# SCH_ACSI2STM_EasyEDA.net
KiCad netlist of a schematic drawn in EasyEDA
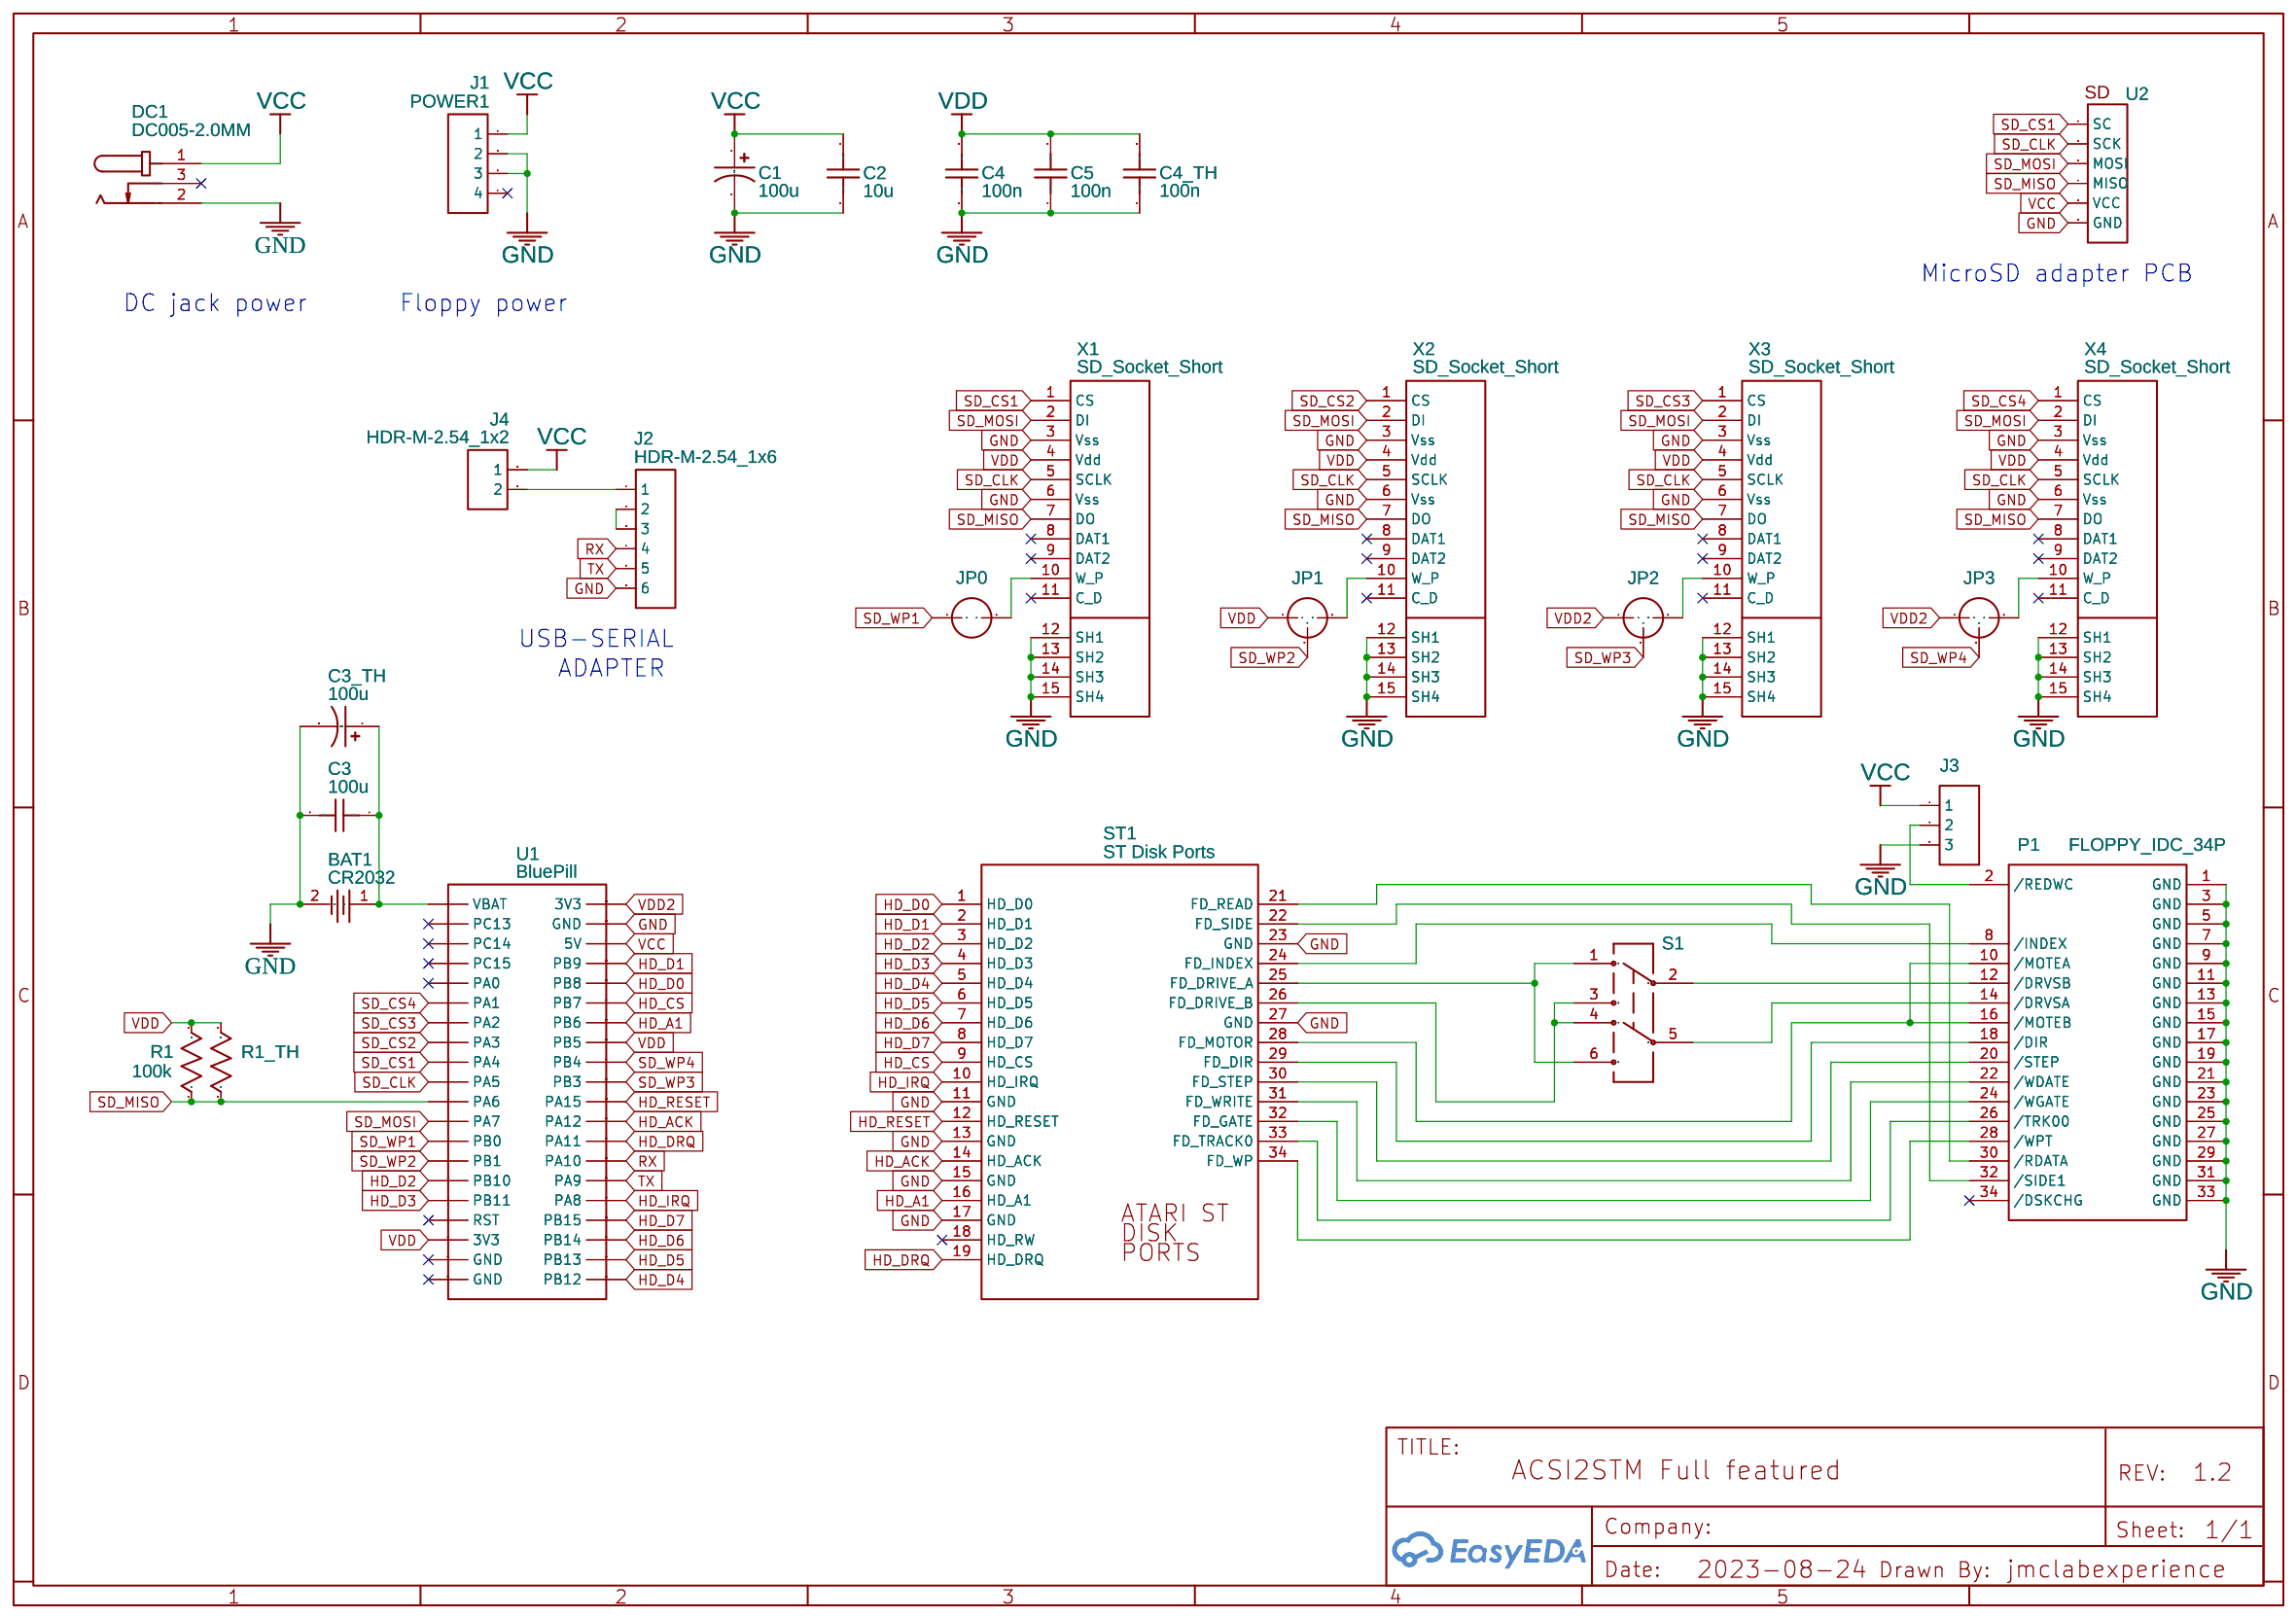
[diagram p0: schematic sheet]

(export (version "E")
  (design (tool "Eeschema 10.0.6"))
  (components
    (comp (ref "BAT1") (value "CR2032") (libsource (lib "") (part "CR2032_C9900007674")))
    (comp (ref "C1") (value "100u") (libsource (lib "") (part "CE_TH_D6.3×F2.5_US_1")))
    (comp (ref "C2") (value "10u") (libsource (lib "") (part "C_1206_US_1")))
    (comp (ref "C3") (value "100u") (libsource (lib "") (part "C_1206_US")))
    (comp (ref "C3_TH") (value "100u") (libsource (lib "") (part "CE_TH_D6.3×F2.5_US")))
    (comp (ref "C4") (value "100n") (libsource (lib "") (part "C_0805_US")))
    (comp (ref "C4_TH") (value "100n") (libsource (lib "") (part "C_RAD-0.2_US")))
    (comp (ref "C5") (value "100n") (libsource (lib "") (part "C_0805_US")))
    (comp (ref "DC1")
      (value "DC005-2.0MM")
      (fields (field (name "Manufacturer") "SOFNG"))
      (libsource (lib "") (part "DC005-2.0MM"))
    )
    (comp (ref "J1") (value "POWER1") (libsource (lib "") (part "HDR-M-2.54_1x4")))
    (comp (ref "J2") (value "HDR-M-2.54_1x6") (libsource (lib "") (part "HDR-M-2.54_1x6")))
    (comp (ref "J3") (value "HDR-M-2.54_1x3") (libsource (lib "") (part "HDR-M-2.54_1x3")))
    (comp (ref "J4") (value "HDR-M-2.54_1x2") (libsource (lib "") (part "HDR-M-2.54_1x2")))
    (comp (ref "JP0") (value "Solder jumper 2P") (libsource (lib "") (part "Solder jumper 2P")))
    (comp (ref "JP1") (value "Solder jumper 3P") (libsource (lib "") (part "Solder jumper 3P")))
    (comp (ref "JP2") (value "Solder jumper 3P") (libsource (lib "") (part "Solder jumper 3P")))
    (comp (ref "JP3") (value "Solder jumper 3P") (libsource (lib "") (part "Solder jumper 3P")))
    (comp (ref "P1")
      (value "FLOPPY_IDC_34P")
      (fields (field (name "Manufacturer Part") "Z-231011034106") (field (name "Manufacturer") "Nextronics"))
      (libsource (lib "") (part "FLOPPY_IDC_34P"))
    )
    (comp (ref "R1") (value "100k") (libsource (lib "") (part "R_0805_US")))
    (comp (ref "R1_TH") (value "1k") (libsource (lib "") (part "R_AXIAL-0.4_US")))
    (comp (ref "S1") (value "SWITCH-DPDT") (libsource (lib "") (part "SWITCH-DPDT")))
    (comp (ref "ST1") (value "ST Disk Ports") (libsource (lib "") (part "ST Disk Ports")))
    (comp (ref "U1") (value "BluePill") (libsource (lib "") (part "BluePill")))
    (comp (ref "U2") (value "SD1") (libsource (lib "") (part "SD")))
    (comp (ref "X1") (value "SD_Socket_Short") (libsource (lib "") (part "SD_Socket_Short")))
    (comp (ref "X2") (value "SD_Socket_Short") (libsource (lib "") (part "SD_Socket_Short")))
    (comp (ref "X3") (value "SD_Socket_Short") (libsource (lib "") (part "SD_Socket_Short")))
    (comp (ref "X4") (value "SD_Socket_Short") (libsource (lib "") (part "SD_Socket_Short")))
  )
  (nets
    (net (code "1") (name "GND") (class "Default")
      (node (ref "BAT1") (pin "2") (pinfunction "2_2") (pintype "input"))
      (node (ref "C1") (pin "2") (pinfunction "2_2") (pintype "unspecified"))
      (node (ref "C2") (pin "1") (pinfunction "1_1") (pintype "unspecified"))
      (node (ref "C3") (pin "2") (pinfunction "2_2") (pintype "unspecified"))
      (node (ref "C3_TH") (pin "2") (pinfunction "2_2") (pintype "unspecified"))
      (node (ref "C4") (pin "1") (pinfunction "1_1") (pintype "unspecified"))
      (node (ref "C4_TH") (pin "1") (pinfunction "1_1") (pintype "unspecified"))
      (node (ref "C5") (pin "1") (pinfunction "1_1") (pintype "unspecified"))
      (node (ref "DC1") (pin "2") (pinfunction "2_2") (pintype "unspecified"))
      (node (ref "J1") (pin "2") (pinfunction "2_2") (pintype "unspecified"))
      (node (ref "J1") (pin "3") (pinfunction "3_3") (pintype "unspecified"))
      (node (ref "J2") (pin "6") (pinfunction "6_6") (pintype "input"))
      (node (ref "J3") (pin "3") (pinfunction "3_3") (pintype "input"))
      (node (ref "P1") (pin "1") (pinfunction "GND_1") (pintype "unspecified"))
      (node (ref "P1") (pin "11") (pinfunction "GND_11") (pintype "unspecified"))
      (node (ref "P1") (pin "13") (pinfunction "GND_13") (pintype "unspecified"))
      (node (ref "P1") (pin "15") (pinfunction "GND_15") (pintype "unspecified"))
      (node (ref "P1") (pin "17") (pinfunction "GND_17") (pintype "unspecified"))
      (node (ref "P1") (pin "19") (pinfunction "GND_19") (pintype "unspecified"))
      (node (ref "P1") (pin "21") (pinfunction "GND_21") (pintype "unspecified"))
      (node (ref "P1") (pin "23") (pinfunction "GND_23") (pintype "unspecified"))
      (node (ref "P1") (pin "25") (pinfunction "GND_25") (pintype "unspecified"))
      (node (ref "P1") (pin "27") (pinfunction "GND_27") (pintype "unspecified"))
      (node (ref "P1") (pin "29") (pinfunction "GND_29") (pintype "unspecified"))
      (node (ref "P1") (pin "3") (pinfunction "GND_3") (pintype "unspecified"))
      (node (ref "P1") (pin "31") (pinfunction "GND_31") (pintype "unspecified"))
      (node (ref "P1") (pin "33") (pinfunction "GND_33") (pintype "unspecified"))
      (node (ref "P1") (pin "5") (pinfunction "GND_5") (pintype "unspecified"))
      (node (ref "P1") (pin "7") (pinfunction "GND_7") (pintype "unspecified"))
      (node (ref "P1") (pin "9") (pinfunction "GND_9") (pintype "unspecified"))
      (node (ref "ST1") (pin "11") (pinfunction "GND_11") (pintype "unspecified"))
      (node (ref "ST1") (pin "13") (pinfunction "GND_13") (pintype "unspecified"))
      (node (ref "ST1") (pin "15") (pinfunction "GND_15") (pintype "unspecified"))
      (node (ref "ST1") (pin "17") (pinfunction "GND_17") (pintype "unspecified"))
      (node (ref "ST1") (pin "23") (pinfunction "GND_23") (pintype "unspecified"))
      (node (ref "ST1") (pin "27") (pinfunction "GND_27") (pintype "unspecified"))
      (node (ref "U1") (pin "GND_3") (pinfunction "GND_GND_3") (pintype "unspecified"))
      (node (ref "U2") (pin "6") (pinfunction "GND_6") (pintype "input"))
      (node (ref "X1") (pin "12") (pinfunction "SH1_12") (pintype "unspecified"))
      (node (ref "X1") (pin "13") (pinfunction "SH2_13") (pintype "unspecified"))
      (node (ref "X1") (pin "14") (pinfunction "SH3_14") (pintype "unspecified"))
      (node (ref "X1") (pin "15") (pinfunction "SH4_15") (pintype "unspecified"))
      (node (ref "X1") (pin "3") (pinfunction "Vss_3") (pintype "unspecified"))
      (node (ref "X1") (pin "6") (pinfunction "Vss_6") (pintype "unspecified"))
      (node (ref "X2") (pin "12") (pinfunction "SH1_12") (pintype "unspecified"))
      (node (ref "X2") (pin "13") (pinfunction "SH2_13") (pintype "unspecified"))
      (node (ref "X2") (pin "14") (pinfunction "SH3_14") (pintype "unspecified"))
      (node (ref "X2") (pin "15") (pinfunction "SH4_15") (pintype "unspecified"))
      (node (ref "X2") (pin "3") (pinfunction "Vss_3") (pintype "unspecified"))
      (node (ref "X2") (pin "6") (pinfunction "Vss_6") (pintype "unspecified"))
      (node (ref "X3") (pin "12") (pinfunction "SH1_12") (pintype "unspecified"))
      (node (ref "X3") (pin "13") (pinfunction "SH2_13") (pintype "unspecified"))
      (node (ref "X3") (pin "14") (pinfunction "SH3_14") (pintype "unspecified"))
      (node (ref "X3") (pin "15") (pinfunction "SH4_15") (pintype "unspecified"))
      (node (ref "X3") (pin "3") (pinfunction "Vss_3") (pintype "unspecified"))
      (node (ref "X3") (pin "6") (pinfunction "Vss_6") (pintype "unspecified"))
      (node (ref "X4") (pin "12") (pinfunction "SH1_12") (pintype "unspecified"))
      (node (ref "X4") (pin "13") (pinfunction "SH2_13") (pintype "unspecified"))
      (node (ref "X4") (pin "14") (pinfunction "SH3_14") (pintype "unspecified"))
      (node (ref "X4") (pin "15") (pinfunction "SH4_15") (pintype "unspecified"))
      (node (ref "X4") (pin "3") (pinfunction "Vss_3") (pintype "unspecified"))
      (node (ref "X4") (pin "6") (pinfunction "Vss_6") (pintype "unspecified"))
    )
    (net (code "2") (name "HD_A1") (class "Default")
      (node (ref "ST1") (pin "16") (pinfunction "HD_A1_16") (pintype "unspecified"))
      (node (ref "U1") (pin "PB6") (pinfunction "PB6_PB6") (pintype "unspecified"))
    )
    (net (code "3") (name "HD_ACK") (class "Default")
      (node (ref "ST1") (pin "14") (pinfunction "HD_ACK_14") (pintype "unspecified"))
      (node (ref "U1") (pin "PA12") (pinfunction "PA12_PA12") (pintype "unspecified"))
    )
    (net (code "4") (name "HD_CS") (class "Default")
      (node (ref "ST1") (pin "9") (pinfunction "HD_CS_9") (pintype "unspecified"))
      (node (ref "U1") (pin "PB7") (pinfunction "PB7_PB7") (pintype "unspecified"))
    )
    (net (code "5") (name "HD_D0") (class "Default")
      (node (ref "ST1") (pin "1") (pinfunction "HD_D0_1") (pintype "unspecified"))
      (node (ref "U1") (pin "PB8") (pinfunction "PB8_PB8") (pintype "unspecified"))
    )
    (net (code "6") (name "HD_D1") (class "Default")
      (node (ref "ST1") (pin "2") (pinfunction "HD_D1_2") (pintype "unspecified"))
      (node (ref "U1") (pin "PB9") (pinfunction "PB9_PB9") (pintype "unspecified"))
    )
    (net (code "7") (name "HD_D2") (class "Default")
      (node (ref "ST1") (pin "3") (pinfunction "HD_D2_3") (pintype "unspecified"))
      (node (ref "U1") (pin "PB10") (pinfunction "PB10_PB10") (pintype "unspecified"))
    )
    (net (code "8") (name "HD_D3") (class "Default")
      (node (ref "ST1") (pin "4") (pinfunction "HD_D3_4") (pintype "unspecified"))
      (node (ref "U1") (pin "PB11") (pinfunction "PB11_PB11") (pintype "unspecified"))
    )
    (net (code "9") (name "HD_D4") (class "Default")
      (node (ref "ST1") (pin "5") (pinfunction "HD_D4_5") (pintype "unspecified"))
      (node (ref "U1") (pin "PB12") (pinfunction "PB12_PB12") (pintype "unspecified"))
    )
    (net (code "10") (name "HD_D5") (class "Default")
      (node (ref "ST1") (pin "6") (pinfunction "HD_D5_6") (pintype "unspecified"))
      (node (ref "U1") (pin "PB13") (pinfunction "PB13_PB13") (pintype "unspecified"))
    )
    (net (code "11") (name "HD_D6") (class "Default")
      (node (ref "ST1") (pin "7") (pinfunction "HD_D6_7") (pintype "unspecified"))
      (node (ref "U1") (pin "PB14") (pinfunction "PB14_PB14") (pintype "unspecified"))
    )
    (net (code "12") (name "HD_D7") (class "Default")
      (node (ref "ST1") (pin "8") (pinfunction "HD_D7_8") (pintype "unspecified"))
      (node (ref "U1") (pin "PB15") (pinfunction "PB15_PB15") (pintype "unspecified"))
    )
    (net (code "13") (name "HD_DRQ") (class "Default")
      (node (ref "ST1") (pin "19") (pinfunction "HD_DRQ_19") (pintype "unspecified"))
      (node (ref "U1") (pin "PA11") (pinfunction "PA11_PA11") (pintype "unspecified"))
    )
    (net (code "14") (name "HD_IRQ") (class "Default")
      (node (ref "ST1") (pin "10") (pinfunction "HD_IRQ_10") (pintype "unspecified"))
      (node (ref "U1") (pin "PA8") (pinfunction "PA8_PA8") (pintype "unspecified"))
    )
    (net (code "15") (name "HD_RESET") (class "Default")
      (node (ref "ST1") (pin "12") (pinfunction "HD_RESET_12") (pintype "unspecified"))
      (node (ref "U1") (pin "PA15") (pinfunction "PA15_PA15") (pintype "unspecified"))
    )
    (net (code "16") (name "Net-(BAT1-Pad1)") (class "Default")
      (node (ref "BAT1") (pin "1") (pinfunction "1_1") (pintype "input"))
      (node (ref "C3") (pin "1") (pinfunction "1_1") (pintype "unspecified"))
      (node (ref "C3_TH") (pin "1") (pinfunction "1_1") (pintype "unspecified"))
      (node (ref "U1") (pin "VBAT") (pinfunction "VBAT_VBAT") (pintype "unspecified"))
    )
    (net (code "17") (name "Net-(J2-Pad1)") (class "Default")
      (node (ref "J2") (pin "1") (pinfunction "1_1") (pintype "input"))
      (node (ref "J4") (pin "2") (pinfunction "2_2") (pintype "unspecified"))
    )
    (net (code "18") (name "Net-(J2-Pad2)") (class "Default")
      (node (ref "J2") (pin "2") (pinfunction "2_2") (pintype "input"))
      (node (ref "J2") (pin "3") (pinfunction "3_3") (pintype "input"))
    )
    (net (code "19") (name "Net-(P1-{slash}DIR)") (class "Default")
      (node (ref "P1") (pin "18") (pinfunction "/DIR_18") (pintype "unspecified"))
      (node (ref "ST1") (pin "29") (pinfunction "FD_DIR_29") (pintype "unspecified"))
    )
    (net (code "20") (name "Net-(P1-{slash}DRVSA)") (class "Default")
      (node (ref "P1") (pin "14") (pinfunction "/DRVSA_14") (pintype "unspecified"))
      (node (ref "S1") (pin "5") (pinfunction "5_5") (pintype "unspecified"))
    )
    (net (code "21") (name "Net-(P1-{slash}DRVSB)") (class "Default")
      (node (ref "P1") (pin "12") (pinfunction "/DRVSB_12") (pintype "unspecified"))
      (node (ref "S1") (pin "2") (pinfunction "2_2") (pintype "unspecified"))
    )
    (net (code "22") (name "Net-(P1-{slash}INDEX)") (class "Default")
      (node (ref "P1") (pin "8") (pinfunction "/INDEX_8") (pintype "unspecified"))
      (node (ref "ST1") (pin "24") (pinfunction "FD_INDEX_24") (pintype "unspecified"))
    )
    (net (code "23") (name "Net-(P1-{slash}MOTEA)") (class "Default")
      (node (ref "P1") (pin "10") (pinfunction "/MOTEA_10") (pintype "unspecified"))
      (node (ref "P1") (pin "16") (pinfunction "/MOTEB_16") (pintype "unspecified"))
      (node (ref "ST1") (pin "28") (pinfunction "FD_MOTOR_28") (pintype "unspecified"))
    )
    (net (code "24") (name "Net-(P1-{slash}RDATA)") (class "Default")
      (node (ref "P1") (pin "30") (pinfunction "/RDATA_30") (pintype "unspecified"))
      (node (ref "ST1") (pin "21") (pinfunction "FD_READ_21") (pintype "unspecified"))
    )
    (net (code "25") (name "Net-(P1-{slash}REDWC)") (class "Default")
      (node (ref "J3") (pin "2") (pinfunction "2_2") (pintype "input"))
      (node (ref "P1") (pin "2") (pinfunction "/REDWC_2") (pintype "unspecified"))
    )
    (net (code "26") (name "Net-(P1-{slash}SIDE1)") (class "Default")
      (node (ref "P1") (pin "32") (pinfunction "/SIDE1_32") (pintype "unspecified"))
      (node (ref "ST1") (pin "22") (pinfunction "FD_SIDE_22") (pintype "unspecified"))
    )
    (net (code "27") (name "Net-(P1-{slash}STEP)") (class "Default")
      (node (ref "P1") (pin "20") (pinfunction "/STEP_20") (pintype "unspecified"))
      (node (ref "ST1") (pin "30") (pinfunction "FD_STEP_30") (pintype "unspecified"))
    )
    (net (code "28") (name "Net-(P1-{slash}TRK00)") (class "Default")
      (node (ref "P1") (pin "26") (pinfunction "/TRK00_26") (pintype "unspecified"))
      (node (ref "ST1") (pin "33") (pinfunction "FD_TRACK0_33") (pintype "unspecified"))
    )
    (net (code "29") (name "Net-(P1-{slash}WDATE)") (class "Default")
      (node (ref "P1") (pin "22") (pinfunction "/WDATE_22") (pintype "unspecified"))
      (node (ref "ST1") (pin "31") (pinfunction "FD_WRITE_31") (pintype "unspecified"))
    )
    (net (code "30") (name "Net-(P1-{slash}WGATE)") (class "Default")
      (node (ref "P1") (pin "24") (pinfunction "/WGATE_24") (pintype "unspecified"))
      (node (ref "ST1") (pin "32") (pinfunction "FD_GATE_32") (pintype "unspecified"))
    )
    (net (code "31") (name "Net-(P1-{slash}WPT)") (class "Default")
      (node (ref "P1") (pin "28") (pinfunction "/WPT_28") (pintype "unspecified"))
      (node (ref "ST1") (pin "34") (pinfunction "FD_WP_34") (pintype "unspecified"))
    )
    (net (code "32") (name "Net-(ST1-FD_DRIVE_A)") (class "Default")
      (node (ref "S1") (pin "1") (pinfunction "1_1") (pintype "unspecified"))
      (node (ref "S1") (pin "6") (pinfunction "6_6") (pintype "unspecified"))
      (node (ref "ST1") (pin "25") (pinfunction "FD_DRIVE_A_25") (pintype "unspecified"))
    )
    (net (code "33") (name "Net-(ST1-FD_DRIVE_B)") (class "Default")
      (node (ref "S1") (pin "3") (pinfunction "3_3") (pintype "unspecified"))
      (node (ref "S1") (pin "4") (pinfunction "4_4") (pintype "unspecified"))
      (node (ref "ST1") (pin "26") (pinfunction "FD_DRIVE_B_26") (pintype "unspecified"))
    )
    (net (code "34") (name "Net-(X1-W_P)") (class "Default")
      (node (ref "JP0") (pin "2") (pinfunction "2_2") (pintype "unspecified"))
      (node (ref "X1") (pin "10") (pinfunction "W_P_10") (pintype "unspecified"))
    )
    (net (code "35") (name "Net-(X2-W_P)") (class "Default")
      (node (ref "JP1") (pin "3") (pinfunction "3_3") (pintype "unspecified"))
      (node (ref "X2") (pin "10") (pinfunction "W_P_10") (pintype "unspecified"))
    )
    (net (code "36") (name "Net-(X3-W_P)") (class "Default")
      (node (ref "JP2") (pin "3") (pinfunction "3_3") (pintype "unspecified"))
      (node (ref "X3") (pin "10") (pinfunction "W_P_10") (pintype "unspecified"))
    )
    (net (code "37") (name "Net-(X4-W_P)") (class "Default")
      (node (ref "JP3") (pin "3") (pinfunction "3_3") (pintype "unspecified"))
      (node (ref "X4") (pin "10") (pinfunction "W_P_10") (pintype "unspecified"))
    )
    (net (code "38") (name "RX") (class "Default")
      (node (ref "J2") (pin "4") (pinfunction "4_4") (pintype "input"))
      (node (ref "U1") (pin "PA10") (pinfunction "PA10_PA10") (pintype "unspecified"))
    )
    (net (code "39") (name "SD_CLK") (class "Default")
      (node (ref "U1") (pin "PA5") (pinfunction "PA5_PA5") (pintype "unspecified"))
      (node (ref "U2") (pin "2") (pinfunction "SCK_2") (pintype "input"))
      (node (ref "X1") (pin "5") (pinfunction "SCLK_5") (pintype "unspecified"))
      (node (ref "X2") (pin "5") (pinfunction "SCLK_5") (pintype "unspecified"))
      (node (ref "X3") (pin "5") (pinfunction "SCLK_5") (pintype "unspecified"))
      (node (ref "X4") (pin "5") (pinfunction "SCLK_5") (pintype "unspecified"))
    )
    (net (code "40") (name "SD_CS1") (class "Default")
      (node (ref "U1") (pin "PA4") (pinfunction "PA4_PA4") (pintype "unspecified"))
      (node (ref "U2") (pin "1") (pinfunction "SC_1") (pintype "input"))
      (node (ref "X1") (pin "1") (pinfunction "CS_1") (pintype "unspecified"))
    )
    (net (code "41") (name "SD_CS2") (class "Default")
      (node (ref "U1") (pin "PA3") (pinfunction "PA3_PA3") (pintype "unspecified"))
      (node (ref "X2") (pin "1") (pinfunction "CS_1") (pintype "unspecified"))
    )
    (net (code "42") (name "SD_CS3") (class "Default")
      (node (ref "U1") (pin "PA2") (pinfunction "PA2_PA2") (pintype "unspecified"))
      (node (ref "X3") (pin "1") (pinfunction "CS_1") (pintype "unspecified"))
    )
    (net (code "43") (name "SD_CS4") (class "Default")
      (node (ref "U1") (pin "PA1") (pinfunction "PA1_PA1") (pintype "unspecified"))
      (node (ref "X4") (pin "1") (pinfunction "CS_1") (pintype "unspecified"))
    )
    (net (code "44") (name "SD_MISO") (class "Default")
      (node (ref "R1") (pin "1") (pinfunction "1_1") (pintype "unspecified"))
      (node (ref "R1_TH") (pin "1") (pinfunction "1_1") (pintype "unspecified"))
      (node (ref "U1") (pin "PA6") (pinfunction "PA6_PA6") (pintype "unspecified"))
      (node (ref "U2") (pin "4") (pinfunction "MISO_4") (pintype "input"))
      (node (ref "X1") (pin "7") (pinfunction "DO_7") (pintype "unspecified"))
      (node (ref "X2") (pin "7") (pinfunction "DO_7") (pintype "unspecified"))
      (node (ref "X3") (pin "7") (pinfunction "DO_7") (pintype "unspecified"))
      (node (ref "X4") (pin "7") (pinfunction "DO_7") (pintype "unspecified"))
    )
    (net (code "45") (name "SD_MOSI") (class "Default")
      (node (ref "U1") (pin "PA7") (pinfunction "PA7_PA7") (pintype "unspecified"))
      (node (ref "U2") (pin "3") (pinfunction "MOSI_3") (pintype "input"))
      (node (ref "X1") (pin "2") (pinfunction "DI_2") (pintype "unspecified"))
      (node (ref "X2") (pin "2") (pinfunction "DI_2") (pintype "unspecified"))
      (node (ref "X3") (pin "2") (pinfunction "DI_2") (pintype "unspecified"))
      (node (ref "X4") (pin "2") (pinfunction "DI_2") (pintype "unspecified"))
    )
    (net (code "46") (name "SD_WP1") (class "Default")
      (node (ref "JP0") (pin "1") (pinfunction "1_1") (pintype "unspecified"))
      (node (ref "U1") (pin "PB0") (pinfunction "PB0_PB0") (pintype "unspecified"))
    )
    (net (code "47") (name "SD_WP2") (class "Default")
      (node (ref "JP1") (pin "2") (pinfunction "2_2") (pintype "unspecified"))
      (node (ref "U1") (pin "PB1") (pinfunction "PB1_PB1") (pintype "unspecified"))
    )
    (net (code "48") (name "SD_WP3") (class "Default")
      (node (ref "JP2") (pin "2") (pinfunction "2_2") (pintype "unspecified"))
      (node (ref "U1") (pin "PB3") (pinfunction "PB3_PB3") (pintype "unspecified"))
    )
    (net (code "49") (name "SD_WP4") (class "Default")
      (node (ref "JP3") (pin "2") (pinfunction "2_2") (pintype "unspecified"))
      (node (ref "U1") (pin "PB4") (pinfunction "PB4_PB4") (pintype "unspecified"))
    )
    (net (code "50") (name "TX") (class "Default")
      (node (ref "J2") (pin "5") (pinfunction "5_5") (pintype "input"))
      (node (ref "U1") (pin "PA9") (pinfunction "PA9_PA9") (pintype "unspecified"))
    )
    (net (code "51") (name "VCC") (class "Default")
      (node (ref "C1") (pin "1") (pinfunction "1_1") (pintype "unspecified"))
      (node (ref "C2") (pin "2") (pinfunction "2_2") (pintype "unspecified"))
      (node (ref "DC1") (pin "1") (pinfunction "1_1") (pintype "unspecified"))
      (node (ref "J1") (pin "1") (pinfunction "1_1") (pintype "unspecified"))
      (node (ref "J3") (pin "1") (pinfunction "1_1") (pintype "input"))
      (node (ref "J4") (pin "1") (pinfunction "1_1") (pintype "unspecified"))
      (node (ref "U1") (pin "5V") (pinfunction "5V_5V") (pintype "unspecified"))
      (node (ref "U2") (pin "5") (pinfunction "VCC_5") (pintype "input"))
    )
    (net (code "52") (name "VDD") (class "Default")
      (node (ref "C4") (pin "2") (pinfunction "2_2") (pintype "unspecified"))
      (node (ref "C4_TH") (pin "2") (pinfunction "2_2") (pintype "unspecified"))
      (node (ref "C5") (pin "2") (pinfunction "2_2") (pintype "unspecified"))
      (node (ref "JP1") (pin "1") (pinfunction "1_1") (pintype "unspecified"))
      (node (ref "R1") (pin "2") (pinfunction "2_2") (pintype "unspecified"))
      (node (ref "R1_TH") (pin "2") (pinfunction "2_2") (pintype "unspecified"))
      (node (ref "U1") (pin "3V3_1") (pinfunction "3V3_3V3_1") (pintype "unspecified"))
      (node (ref "U1") (pin "PB5") (pinfunction "PB5_PB5") (pintype "unspecified"))
      (node (ref "X1") (pin "4") (pinfunction "Vdd_4") (pintype "unspecified"))
      (node (ref "X2") (pin "4") (pinfunction "Vdd_4") (pintype "unspecified"))
      (node (ref "X3") (pin "4") (pinfunction "Vdd_4") (pintype "unspecified"))
      (node (ref "X4") (pin "4") (pinfunction "Vdd_4") (pintype "unspecified"))
    )
    (net (code "53") (name "VDD2") (class "Default")
      (node (ref "JP2") (pin "1") (pinfunction "1_1") (pintype "unspecified"))
      (node (ref "JP3") (pin "1") (pinfunction "1_1") (pintype "unspecified"))
      (node (ref "U1") (pin "3V3_2") (pinfunction "3V3_3V3_2") (pintype "unspecified"))
    )
    (net (code "54") (name "unconnected-(DC1-Pad3)") (class "Default")
      (node (ref "DC1") (pin "3") (pinfunction "3_3") (pintype "unspecified+no_connect"))
    )
    (net (code "55") (name "unconnected-(J1-Pad4)") (class "Default")
      (node (ref "J1") (pin "4") (pinfunction "4_4") (pintype "unspecified+no_connect"))
    )
    (net (code "56") (name "unconnected-(P1-{slash}DSKCHG-Pad34)") (class "Default")
      (node (ref "P1") (pin "34") (pinfunction "/DSKCHG_34") (pintype "unspecified+no_connect"))
    )
    (net (code "57") (name "unconnected-(ST1-HD_RW-Pad18)") (class "Default")
      (node (ref "ST1") (pin "18") (pinfunction "HD_RW_18") (pintype "unspecified+no_connect"))
    )
    (net (code "58") (name "unconnected-(U1-GND-PadGND_1)") (class "Default")
      (node (ref "U1") (pin "GND_1") (pinfunction "GND_GND_1") (pintype "unspecified+no_connect"))
    )
    (net (code "59") (name "unconnected-(U1-GND-PadGND_2)") (class "Default")
      (node (ref "U1") (pin "GND_2") (pinfunction "GND_GND_2") (pintype "unspecified+no_connect"))
    )
    (net (code "60") (name "unconnected-(U1-PadPA0)") (class "Default")
      (node (ref "U1") (pin "PA0") (pinfunction "PA0_PA0") (pintype "unspecified+no_connect"))
    )
    (net (code "61") (name "unconnected-(U1-PadPC13)") (class "Default")
      (node (ref "U1") (pin "PC13") (pinfunction "PC13_PC13") (pintype "unspecified+no_connect"))
    )
    (net (code "62") (name "unconnected-(U1-PadPC14)") (class "Default")
      (node (ref "U1") (pin "PC14") (pinfunction "PC14_PC14") (pintype "unspecified+no_connect"))
    )
    (net (code "63") (name "unconnected-(U1-PadPC15)") (class "Default")
      (node (ref "U1") (pin "PC15") (pinfunction "PC15_PC15") (pintype "unspecified+no_connect"))
    )
    (net (code "64") (name "unconnected-(U1-PadRST)") (class "Default")
      (node (ref "U1") (pin "RST") (pinfunction "RST_RST") (pintype "unspecified+no_connect"))
    )
    (net (code "65") (name "unconnected-(X1-C_D-Pad11)") (class "Default")
      (node (ref "X1") (pin "11") (pinfunction "C_D_11") (pintype "unspecified+no_connect"))
    )
    (net (code "66") (name "unconnected-(X1-DAT1-Pad8)") (class "Default")
      (node (ref "X1") (pin "8") (pinfunction "DAT1_8") (pintype "unspecified+no_connect"))
    )
    (net (code "67") (name "unconnected-(X1-DAT2-Pad9)") (class "Default")
      (node (ref "X1") (pin "9") (pinfunction "DAT2_9") (pintype "unspecified+no_connect"))
    )
    (net (code "68") (name "unconnected-(X2-C_D-Pad11)") (class "Default")
      (node (ref "X2") (pin "11") (pinfunction "C_D_11") (pintype "unspecified+no_connect"))
    )
    (net (code "69") (name "unconnected-(X2-DAT1-Pad8)") (class "Default")
      (node (ref "X2") (pin "8") (pinfunction "DAT1_8") (pintype "unspecified+no_connect"))
    )
    (net (code "70") (name "unconnected-(X2-DAT2-Pad9)") (class "Default")
      (node (ref "X2") (pin "9") (pinfunction "DAT2_9") (pintype "unspecified+no_connect"))
    )
    (net (code "71") (name "unconnected-(X3-C_D-Pad11)") (class "Default")
      (node (ref "X3") (pin "11") (pinfunction "C_D_11") (pintype "unspecified+no_connect"))
    )
    (net (code "72") (name "unconnected-(X3-DAT1-Pad8)") (class "Default")
      (node (ref "X3") (pin "8") (pinfunction "DAT1_8") (pintype "unspecified+no_connect"))
    )
    (net (code "73") (name "unconnected-(X3-DAT2-Pad9)") (class "Default")
      (node (ref "X3") (pin "9") (pinfunction "DAT2_9") (pintype "unspecified+no_connect"))
    )
    (net (code "74") (name "unconnected-(X4-C_D-Pad11)") (class "Default")
      (node (ref "X4") (pin "11") (pinfunction "C_D_11") (pintype "unspecified+no_connect"))
    )
    (net (code "75") (name "unconnected-(X4-DAT1-Pad8)") (class "Default")
      (node (ref "X4") (pin "8") (pinfunction "DAT1_8") (pintype "unspecified+no_connect"))
    )
    (net (code "76") (name "unconnected-(X4-DAT2-Pad9)") (class "Default")
      (node (ref "X4") (pin "9") (pinfunction "DAT2_9") (pintype "unspecified+no_connect"))
    )
  )
)
